# lcd_booster_mk3.net
KiCad netlist of a schematic drawn in EAGLE
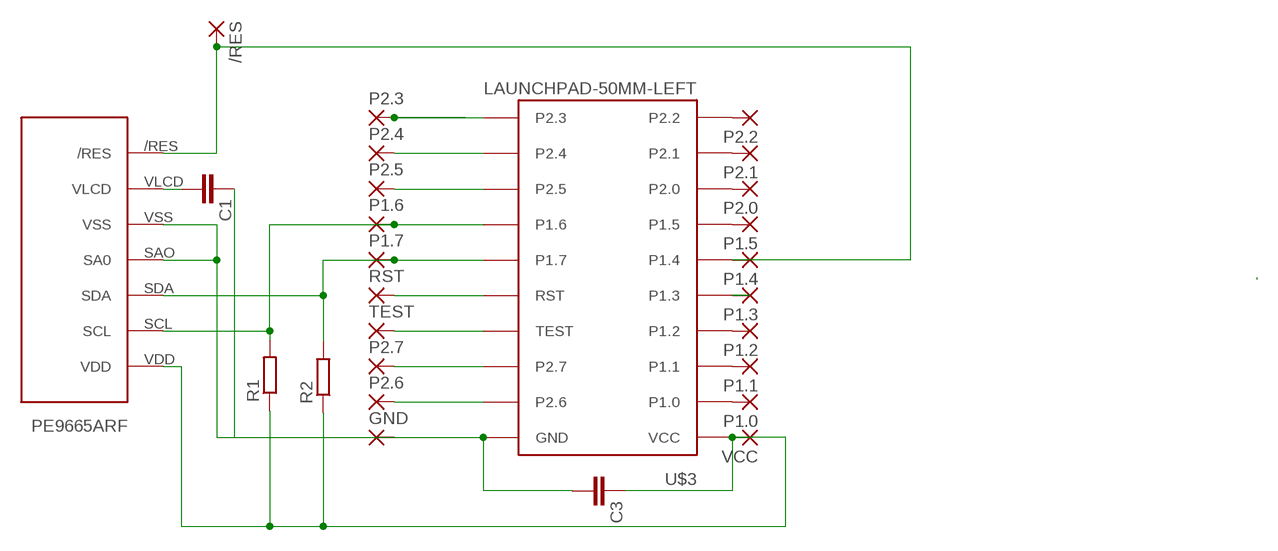
[diagram p0: schematic, sheet 1]

(export (version "E")
  (design (tool "Eeschema 10.0.6"))
  (components
    (comp (ref "/RES")
      (value "1,6/0,9")
      (footprint "eagle-import:1,6_0,9")
      (libsource (lib "eagle-import") (part "1,6/0,9"))
    )
    (comp (ref "C1")
      (value "C-EUC1206")
      (footprint "eagle-import:C1206")
      (libsource (lib "eagle-import") (part "C-EUC1206"))
    )
    (comp (ref "C3")
      (value "C-EUC1206")
      (footprint "eagle-import:C1206")
      (libsource (lib "eagle-import") (part "C-EUC1206"))
    )
    (comp (ref "GND")
      (value "1,6/0,9")
      (footprint "eagle-import:1,6_0,9")
      (libsource (lib "eagle-import") (part "1,6/0,9"))
    )
    (comp (ref "P1.0")
      (value "1,6/0,9")
      (footprint "eagle-import:1,6_0,9")
      (libsource (lib "eagle-import") (part "1,6/0,9"))
    )
    (comp (ref "P1.1")
      (value "1,6/0,9")
      (footprint "eagle-import:1,6_0,9")
      (libsource (lib "eagle-import") (part "1,6/0,9"))
    )
    (comp (ref "P1.2")
      (value "1,6/0,9")
      (footprint "eagle-import:1,6_0,9")
      (libsource (lib "eagle-import") (part "1,6/0,9"))
    )
    (comp (ref "P1.3")
      (value "1,6/0,9")
      (footprint "eagle-import:1,6_0,9")
      (libsource (lib "eagle-import") (part "1,6/0,9"))
    )
    (comp (ref "P1.4")
      (value "1,6/0,9")
      (footprint "eagle-import:1,6_0,9")
      (libsource (lib "eagle-import") (part "1,6/0,9"))
    )
    (comp (ref "P1.5")
      (value "1,6/0,9")
      (footprint "eagle-import:1,6_0,9")
      (libsource (lib "eagle-import") (part "1,6/0,9"))
    )
    (comp (ref "P1.6")
      (value "1,6/0,9")
      (footprint "eagle-import:1,6_0,9")
      (libsource (lib "eagle-import") (part "1,6/0,9"))
    )
    (comp (ref "P1.7")
      (value "1,6/0,9")
      (footprint "eagle-import:1,6_0,9")
      (libsource (lib "eagle-import") (part "1,6/0,9"))
    )
    (comp (ref "P2.0")
      (value "SMD2")
      (footprint "eagle-import:SMD1,27-2,54")
      (libsource (lib "eagle-import") (part "SMD2"))
    )
    (comp (ref "P2.1")
      (value "SMD2")
      (footprint "eagle-import:SMD1,27-2,54")
      (libsource (lib "eagle-import") (part "SMD2"))
    )
    (comp (ref "P2.2")
      (value "1,6/0,9")
      (footprint "eagle-import:1,6_0,9")
      (libsource (lib "eagle-import") (part "1,6/0,9"))
    )
    (comp (ref "P2.3")
      (value "1,6/0,9")
      (footprint "eagle-import:1,6_0,9")
      (libsource (lib "eagle-import") (part "1,6/0,9"))
    )
    (comp (ref "P2.4")
      (value "SMD2")
      (footprint "eagle-import:SMD1,27-2,54")
      (libsource (lib "eagle-import") (part "SMD2"))
    )
    (comp (ref "P2.5")
      (value "SMD2")
      (footprint "eagle-import:SMD1,27-2,54")
      (libsource (lib "eagle-import") (part "SMD2"))
    )
    (comp (ref "P2.6")
      (value "1,6/0,9")
      (footprint "eagle-import:1,6_0,9")
      (libsource (lib "eagle-import") (part "1,6/0,9"))
    )
    (comp (ref "P2.7")
      (value "1,6/0,9")
      (footprint "eagle-import:1,6_0,9")
      (libsource (lib "eagle-import") (part "1,6/0,9"))
    )
    (comp (ref "R1")
      (value "R-EU_M1206")
      (footprint "eagle-import:M1206")
      (libsource (lib "eagle-import") (part "R-EU_M1206"))
    )
    (comp (ref "R2")
      (value "R-EU_M1206")
      (footprint "eagle-import:M1206")
      (libsource (lib "eagle-import") (part "R-EU_M1206"))
    )
    (comp (ref "RST")
      (value "1,6/0,9")
      (footprint "eagle-import:1,6_0,9")
      (libsource (lib "eagle-import") (part "1,6/0,9"))
    )
    (comp (ref "TEST")
      (value "1,6/0,9")
      (footprint "eagle-import:1,6_0,9")
      (libsource (lib "eagle-import") (part "1,6/0,9"))
    )
    (comp (ref "U$2")
      (value "PE9665ARF")
      (footprint "eagle-import:PE9665ARF")
      (libsource (lib "eagle-import") (part "PE9665ARF"))
    )
    (comp (ref "U$3")
      (value "LAUNCHPAD-50MM-LEFT")
      (footprint "eagle-import:LAUNCHPAD-50MM-LEFT")
      (libsource (lib "eagle-import") (part "LAUNCHPAD-50MM-LEFT"))
    )
    (comp (ref "VCC")
      (value "1,6/0,9")
      (footprint "eagle-import:1,6_0,9")
      (libsource (lib "eagle-import") (part "1,6/0,9"))
    )
  )
  (nets
    (net (code "1") (name "/TEST") (class "Default")
      (node (ref "TEST") (pin "1") (pinfunction "P_1") (pintype "passive"))
      (node (ref "U$3") (pin "TEST") (pinfunction "TEST_TEST") (pintype "bidirectional"))
    )
    (net (code "2") (name "Net-(/RES-P)") (class "Default")
      (node (ref "/RES") (pin "1") (pinfunction "P_1") (pintype "passive"))
      (node (ref "P1.4") (pin "1") (pinfunction "P_1") (pintype "passive"))
      (node (ref "U$2") (pin "/RES") (pinfunction "/RES_/RES") (pintype "bidirectional"))
      (node (ref "U$3") (pin "P1.4") (pinfunction "P1.4_P1.4") (pintype "bidirectional"))
    )
    (net (code "3") (name "Net-(C1-Pad2)") (class "Default")
      (node (ref "C1") (pin "2") (pinfunction "2_2") (pintype "passive"))
      (node (ref "U$2") (pin "VLCD") (pinfunction "VLCD_VLCD") (pintype "bidirectional"))
    )
    (net (code "4") (name "Net-(GND-P)") (class "Default")
      (node (ref "C1") (pin "1") (pinfunction "1_1") (pintype "passive"))
      (node (ref "C3") (pin "2") (pinfunction "2_2") (pintype "passive"))
      (node (ref "GND") (pin "1") (pinfunction "P_1") (pintype "passive"))
      (node (ref "U$2") (pin "SAO") (pinfunction "SA0_SAO") (pintype "bidirectional"))
      (node (ref "U$2") (pin "VSS") (pinfunction "VSS_VSS") (pintype "power_in"))
      (node (ref "U$3") (pin "GND") (pinfunction "GND_GND") (pintype "power_in"))
    )
    (net (code "5") (name "Net-(P1.0-P)") (class "Default")
      (node (ref "P1.0") (pin "1") (pinfunction "P_1") (pintype "passive"))
      (node (ref "U$3") (pin "P1.0") (pinfunction "P1.0_P1.0") (pintype "bidirectional"))
    )
    (net (code "6") (name "Net-(P1.1-P)") (class "Default")
      (node (ref "P1.1") (pin "1") (pinfunction "P_1") (pintype "passive"))
      (node (ref "U$3") (pin "P1.1") (pinfunction "P1.1_P1.1") (pintype "bidirectional"))
    )
    (net (code "7") (name "Net-(P1.2-P)") (class "Default")
      (node (ref "P1.2") (pin "1") (pinfunction "P_1") (pintype "passive"))
      (node (ref "U$3") (pin "P1.2") (pinfunction "P1.2_P1.2") (pintype "bidirectional"))
    )
    (net (code "8") (name "Net-(P1.3-P)") (class "Default")
      (node (ref "P1.3") (pin "1") (pinfunction "P_1") (pintype "passive"))
      (node (ref "U$3") (pin "P1.3") (pinfunction "P1.3_P1.3") (pintype "bidirectional"))
    )
    (net (code "9") (name "Net-(P1.5-P)") (class "Default")
      (node (ref "P1.5") (pin "1") (pinfunction "P_1") (pintype "passive"))
      (node (ref "U$3") (pin "P1.5") (pinfunction "P1.5_P1.5") (pintype "bidirectional"))
    )
    (net (code "10") (name "Net-(P1.6-P)") (class "Default")
      (node (ref "P1.6") (pin "1") (pinfunction "P_1") (pintype "passive"))
      (node (ref "R1") (pin "2") (pinfunction "2_2") (pintype "passive"))
      (node (ref "U$2") (pin "SCL") (pinfunction "SCL_SCL") (pintype "bidirectional"))
      (node (ref "U$3") (pin "P1.6") (pinfunction "P1.6_P1.6") (pintype "bidirectional"))
    )
    (net (code "11") (name "Net-(P1.7-P)") (class "Default")
      (node (ref "P1.7") (pin "1") (pinfunction "P_1") (pintype "passive"))
      (node (ref "R2") (pin "2") (pinfunction "2_2") (pintype "passive"))
      (node (ref "U$2") (pin "SDA") (pinfunction "SDA_SDA") (pintype "bidirectional"))
      (node (ref "U$3") (pin "P1.7") (pinfunction "P1.7_P1.7") (pintype "bidirectional"))
    )
    (net (code "12") (name "Net-(P2.0-P)") (class "Default")
      (node (ref "P2.0") (pin "1") (pinfunction "P_1") (pintype "passive"))
      (node (ref "U$3") (pin "P2.0") (pinfunction "P2.0_P2.0") (pintype "bidirectional"))
    )
    (net (code "13") (name "Net-(P2.1-P)") (class "Default")
      (node (ref "P2.1") (pin "1") (pinfunction "P_1") (pintype "passive"))
      (node (ref "U$3") (pin "P2.1") (pinfunction "P2.1_P2.1") (pintype "bidirectional"))
    )
    (net (code "14") (name "Net-(P2.2-P)") (class "Default")
      (node (ref "P2.2") (pin "1") (pinfunction "P_1") (pintype "passive"))
      (node (ref "U$3") (pin "P2.2") (pinfunction "P2.2_P2.2") (pintype "bidirectional"))
    )
    (net (code "15") (name "Net-(P2.3-P)") (class "Default")
      (node (ref "P2.3") (pin "1") (pinfunction "P_1") (pintype "passive"))
      (node (ref "U$3") (pin "P2.3") (pinfunction "P2.3_P2.3") (pintype "bidirectional"))
    )
    (net (code "16") (name "Net-(P2.4-P)") (class "Default")
      (node (ref "P2.4") (pin "1") (pinfunction "P_1") (pintype "passive"))
      (node (ref "U$3") (pin "P2.4") (pinfunction "P2.4_P2.4") (pintype "bidirectional"))
    )
    (net (code "17") (name "Net-(P2.5-P)") (class "Default")
      (node (ref "P2.5") (pin "1") (pinfunction "P_1") (pintype "passive"))
      (node (ref "U$3") (pin "P2.5") (pinfunction "P2.5_P2.5") (pintype "bidirectional"))
    )
    (net (code "18") (name "Net-(P2.6-P)") (class "Default")
      (node (ref "P2.6") (pin "1") (pinfunction "P_1") (pintype "passive"))
      (node (ref "U$3") (pin "P2.6") (pinfunction "P2.6_P2.6") (pintype "bidirectional"))
    )
    (net (code "19") (name "Net-(P2.7-P)") (class "Default")
      (node (ref "P2.7") (pin "1") (pinfunction "P_1") (pintype "passive"))
      (node (ref "U$3") (pin "P2.7") (pinfunction "P2.7_P2.7") (pintype "bidirectional"))
    )
    (net (code "20") (name "Net-(RST-P)") (class "Default")
      (node (ref "RST") (pin "1") (pinfunction "P_1") (pintype "passive"))
      (node (ref "U$3") (pin "RST") (pinfunction "RST_RST") (pintype "bidirectional"))
    )
    (net (code "21") (name "Net-(VCC-P)") (class "Default")
      (node (ref "C3") (pin "1") (pinfunction "1_1") (pintype "passive"))
      (node (ref "R1") (pin "1") (pinfunction "1_1") (pintype "passive"))
      (node (ref "R2") (pin "1") (pinfunction "1_1") (pintype "passive"))
      (node (ref "U$2") (pin "VDD") (pinfunction "VDD_VDD") (pintype "power_in"))
      (node (ref "U$3") (pin "VCC") (pinfunction "VCC_VCC") (pintype "power_in"))
      (node (ref "VCC") (pin "1") (pinfunction "P_1") (pintype "passive"))
    )
  )
)
